# Test_Pour_Over_1.net
KiCad netlist of a schematic drawn in Altium Designer
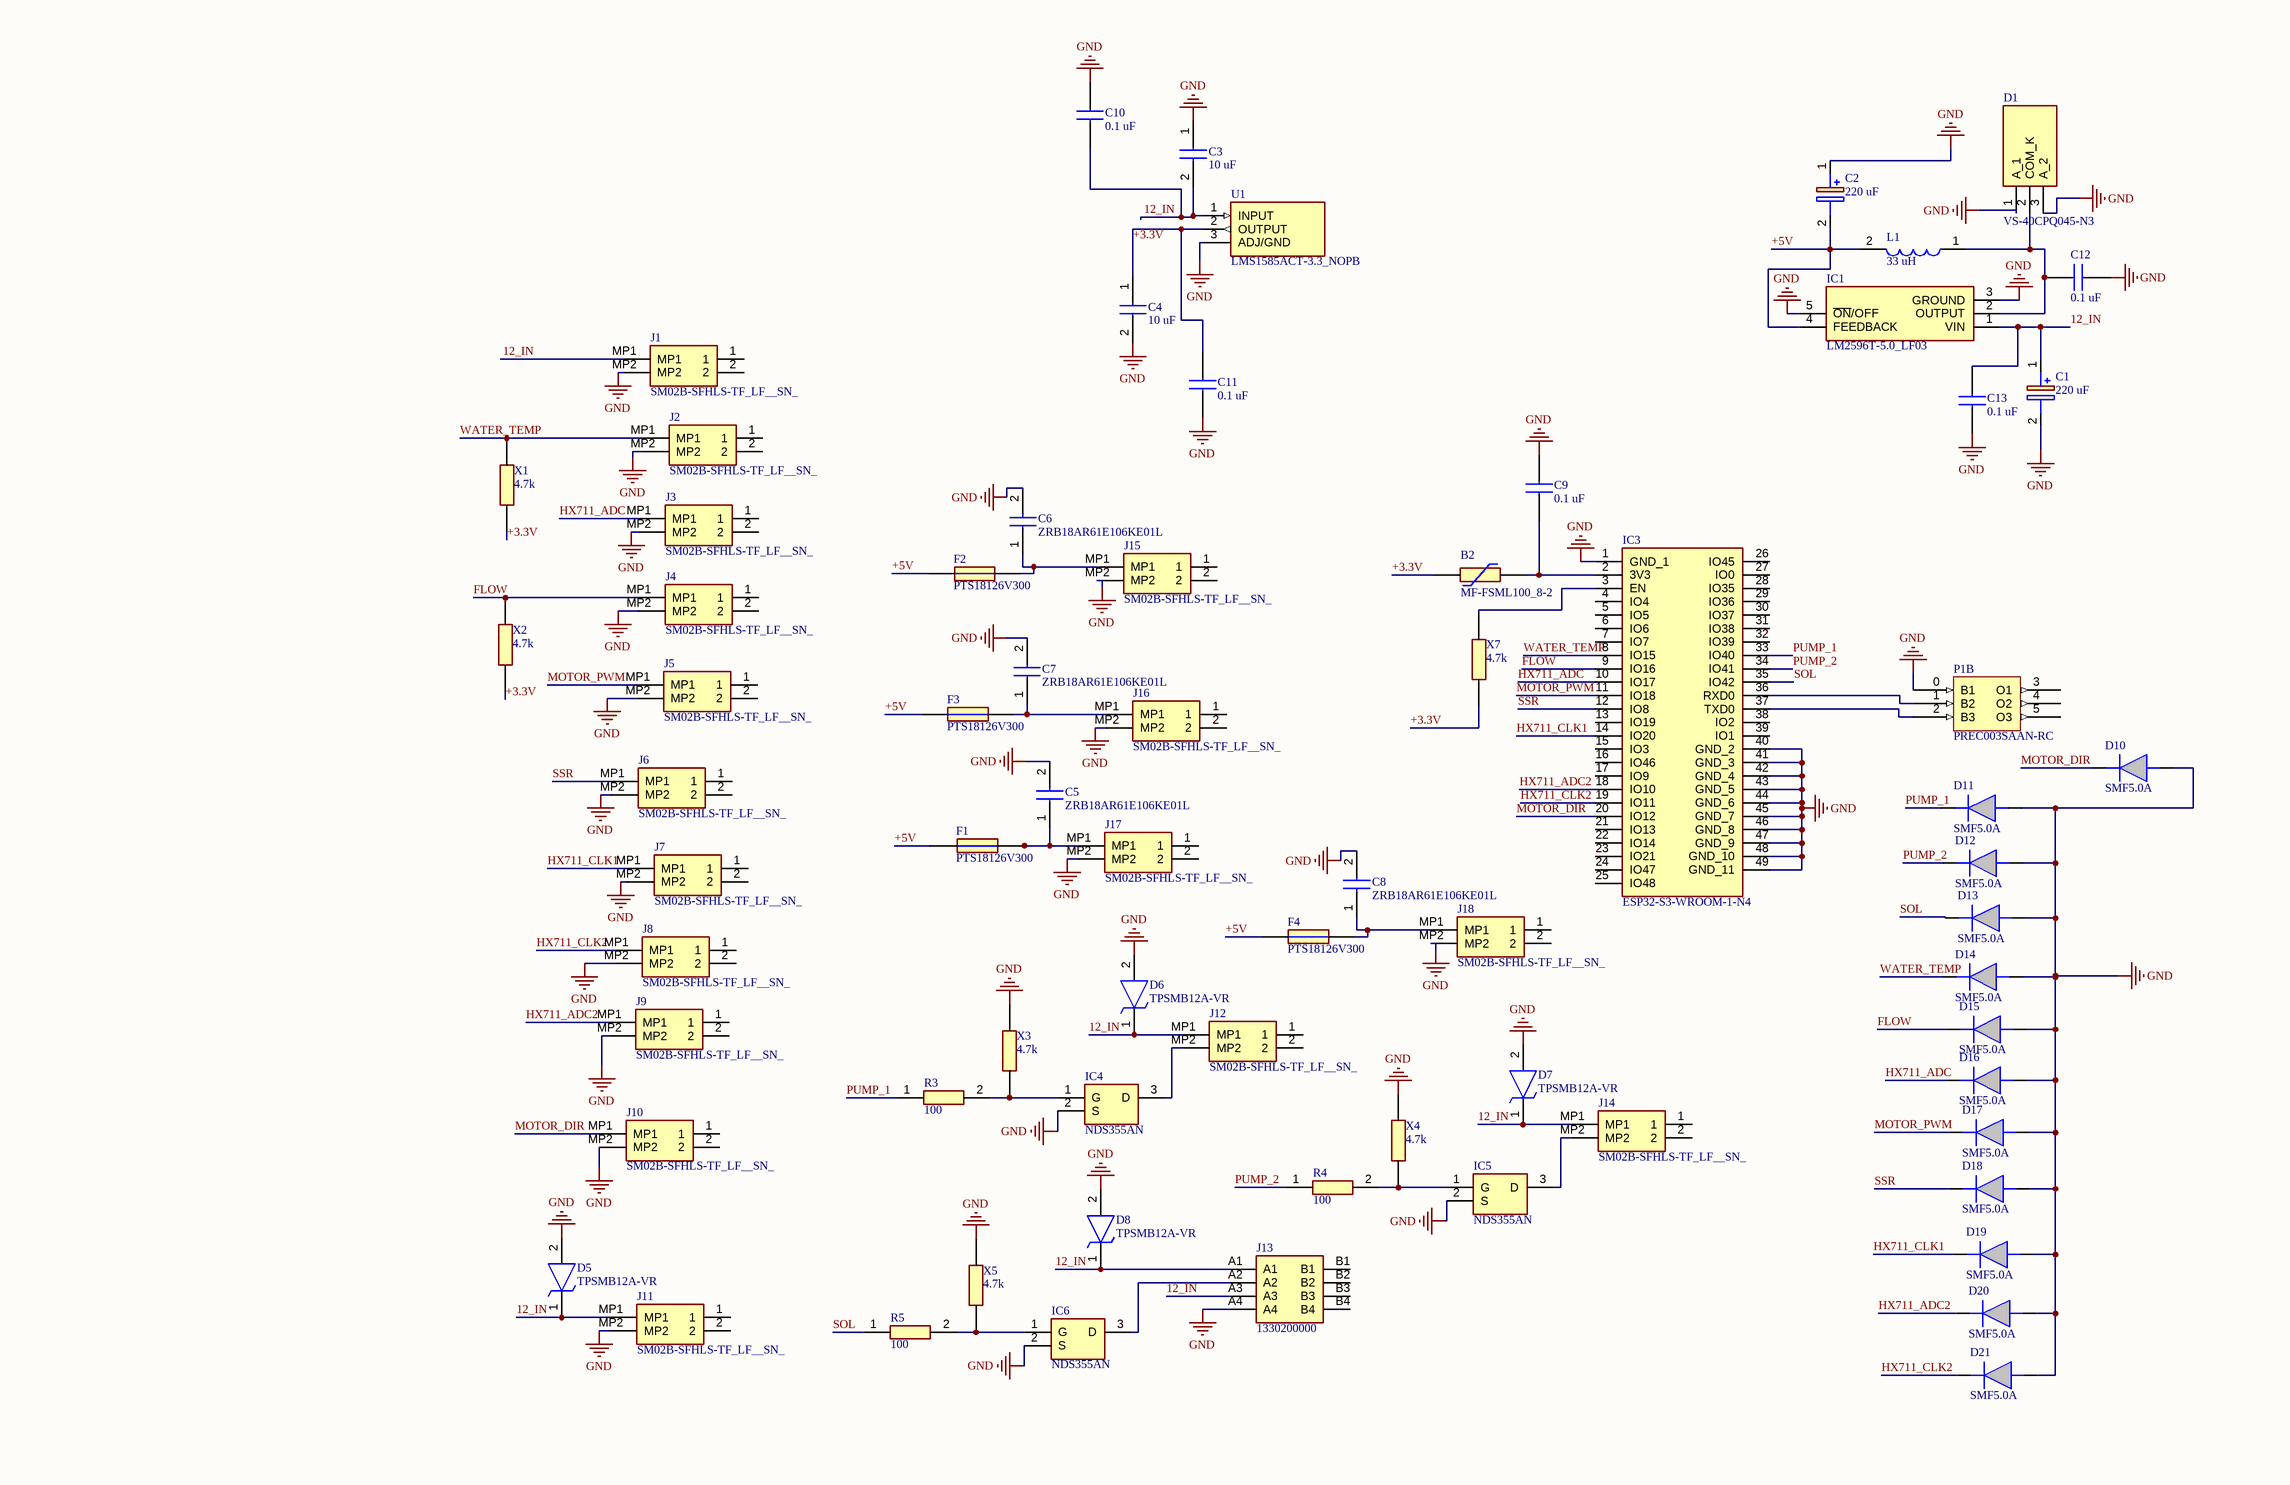
[diagram p0: Test Pour Over 1.SchDoc]

(export (version "E")
  (design (tool "Eeschema 10.0.6"))
  (components
    (comp (ref "B2")
      (value "MF-FSML100_8-2")
      (footprint "Footprints:FUSC1608X70N")
      (description "Resettable Fuses - PPTC 8V     1A")
      (fields
        (field (name "MOUSER PART NUMBER") "652-MF-FSML100/8-2")
        (field (name "MANUFACTURER_PART_NUMBER") "MF-FSML100/8-2")
      )
      (libsource (lib "Pour Over 1") (part "MF-FSML100_8-2"))
    )
    (comp (ref "C1")
      (value "220 uF")
      (footprint "Footprints:EEHZT1E331UP")
      (description "Capacitor Polarised")
      (fields
        (field (name "MANUFACTURER_PART_NUMBER") "EEE-TP1C221AP")
        (field (name "MOUSER PART NUMBER") "667-EEE-TP1C221AP")
      )
      (libsource (lib "*") (part "EEE-TP1C221AP"))
    )
    (comp (ref "C2")
      (value "220 uF")
      (footprint "Footprints:EEHZT1E331UP")
      (description "Capacitor Polarised")
      (fields
        (field (name "MANUFACTURER_PART_NUMBER") "EEE-TP1C221AP")
        (field (name "MOUSER PART NUMBER") "667-EEE-TP1C221AP")
      )
      (libsource (lib "*") (part "EEE-TP1C221AP"))
    )
    (comp (ref "C3")
      (value "10 uF")
      (footprint "Footprints:ZRB18x")
      (fields (field (name "MANUFACTURER_PART_NUMBER") "ZRB18AR61E106KE01L"))
      (libsource (lib "Pour Over 1") (part "ZRB18AR61E106KE01L"))
    )
    (comp (ref "C4")
      (value "10 uF")
      (footprint "Footprints:ZRB18x")
      (fields (field (name "MANUFACTURER_PART_NUMBER") "ZRB18AR61E106KE01L"))
      (libsource (lib "Pour Over 1") (part "ZRB18AR61E106KE01L"))
    )
    (comp (ref "C5")
      (value "ZRB18AR61E106KE01L")
      (footprint "Footprints:ZRB18x")
      (description "Capacitor")
      (libsource (lib "Pour Over 1") (part "ZRB18AR61E106KE01L"))
    )
    (comp (ref "C6")
      (value "ZRB18AR61E106KE01L")
      (footprint "Footprints:ZRB18x")
      (description "Capacitor")
      (libsource (lib "Pour Over 1") (part "ZRB18AR61E106KE01L"))
    )
    (comp (ref "C7")
      (value "ZRB18AR61E106KE01L")
      (footprint "Footprints:ZRB18x")
      (description "Capacitor")
      (libsource (lib "Pour Over 1") (part "ZRB18AR61E106KE01L"))
    )
    (comp (ref "C8")
      (value "ZRB18AR61E106KE01L")
      (footprint "Footprints:ZRB18x")
      (description "Capacitor")
      (libsource (lib "Pour Over 1") (part "ZRB18AR61E106KE01L"))
    )
    (comp (ref "C9")
      (value "0.1 uF")
      (footprint "Footprints:CAPC2012X125N")
      (fields
        (field (name "MOUSER PART NUMBER") "710-885382207007")
        (field (name "MANUFACTURER_PART_NUMBER") "885382207007")
      )
      (libsource (lib "Pour Over 1") (part "885382207007"))
    )
    (comp (ref "C10")
      (value "0.1 uF")
      (footprint "CAPC2012X125N")
      (fields
        (field (name "MOUSER PART NUMBER") "710-885382207007")
        (field (name "MANUFACTURER_PART_NUMBER") "885382207007")
      )
      (libsource (lib "Pour Over 1") (part "885382207007"))
    )
    (comp (ref "C11")
      (value "0.1 uF")
      (footprint "CAPC2012X125N")
      (fields
        (field (name "MOUSER PART NUMBER") "710-885382207007")
        (field (name "MANUFACTURER_PART_NUMBER") "885382207007")
      )
      (libsource (lib "Pour Over 1") (part "885382207007"))
    )
    (comp (ref "C12")
      (value "0.1 uF")
      (footprint "CAPC2012X125N")
      (fields
        (field (name "MOUSER PART NUMBER") "710-885382207007")
        (field (name "MANUFACTURER_PART_NUMBER") "885382207007")
      )
      (libsource (lib "Pour Over 1") (part "885382207007"))
    )
    (comp (ref "C13")
      (value "0.1 uF")
      (footprint "CAPC2012X125N")
      (fields
        (field (name "MOUSER PART NUMBER") "710-885382207007")
        (field (name "MANUFACTURER_PART_NUMBER") "885382207007")
      )
      (libsource (lib "Pour Over 1") (part "885382207007"))
    )
    (comp (ref "D1")
      (value "VS-40CPQ045-N3")
      (footprint "Footprints:TO546P531X1558X2499-3P")
      (description "Diode")
      (fields (field (name "MOUSER PART NUMBER") "78-VS-40CPQ045-N3"))
      (libsource (lib "SamacSys") (part "VS-40CPQ045-N3"))
    )
    (comp (ref "D5")
      (value "TPSMB12A-VR")
      (footprint "SamacSys:DIOM5436X244N")
      (description "TVS Diode (Uni-directional)")
      (fields (field (name "MOUSER PART NUMBER") "576-TPSMB12A-VR"))
      (libsource (lib "*") (part "TPSMB12A-VR"))
    )
    (comp (ref "D6")
      (value "TPSMB12A-VR")
      (footprint "SamacSys:DIOM5436X244N")
      (description "TVS Diode (Uni-directional)")
      (fields (field (name "MOUSER PART NUMBER") "576-TPSMB12A-VR"))
      (libsource (lib "*") (part "TPSMB12A-VR"))
    )
    (comp (ref "D7")
      (value "TPSMB12A-VR")
      (footprint "SamacSys:DIOM5436X244N")
      (description "TVS Diode (Uni-directional)")
      (fields (field (name "MOUSER PART NUMBER") "576-TPSMB12A-VR"))
      (libsource (lib "*") (part "TPSMB12A-VR"))
    )
    (comp (ref "D8")
      (value "TPSMB12A-VR")
      (footprint "SamacSys:DIOM5436X244N")
      (description "TVS Diode (Uni-directional)")
      (fields (field (name "MOUSER PART NUMBER") "576-TPSMB12A-VR"))
      (libsource (lib "*") (part "TPSMB12A-VR"))
    )
    (comp (ref "D10")
      (value "SMF5.0A")
      (footprint "Footprints:SODFL3618X110N")
      (description "LITTELFUSE - SMF5.0A - TVS DIODE, 200W, 5V, UNIDIR, SOD-123FL")
      (fields (field (name "MOUSER PART NUMBER") "576-SMF5.0A"))
      (libsource (lib "Pour Over 1") (part "SMF5.0A"))
    )
    (comp (ref "D11")
      (value "SMF5.0A")
      (footprint "Footprints:SODFL3618X110N")
      (description "LITTELFUSE - SMF5.0A - TVS DIODE, 200W, 5V, UNIDIR, SOD-123FL")
      (fields (field (name "MOUSER PART NUMBER") "576-SMF5.0A"))
      (libsource (lib "Pour Over 1") (part "SMF5.0A"))
    )
    (comp (ref "D12")
      (value "SMF5.0A")
      (footprint "Footprints:SODFL3618X110N")
      (description "LITTELFUSE - SMF5.0A - TVS DIODE, 200W, 5V, UNIDIR, SOD-123FL")
      (fields (field (name "MOUSER PART NUMBER") "576-SMF5.0A"))
      (libsource (lib "Pour Over 1") (part "SMF5.0A"))
    )
    (comp (ref "D13")
      (value "SMF5.0A")
      (footprint "Footprints:SODFL3618X110N")
      (description "LITTELFUSE - SMF5.0A - TVS DIODE, 200W, 5V, UNIDIR, SOD-123FL")
      (fields (field (name "MOUSER PART NUMBER") "576-SMF5.0A"))
      (libsource (lib "Pour Over 1") (part "SMF5.0A"))
    )
    (comp (ref "D14")
      (value "SMF5.0A")
      (footprint "Footprints:SODFL3618X110N")
      (description "LITTELFUSE - SMF5.0A - TVS DIODE, 200W, 5V, UNIDIR, SOD-123FL")
      (fields (field (name "MOUSER PART NUMBER") "576-SMF5.0A"))
      (libsource (lib "Pour Over 1") (part "SMF5.0A"))
    )
    (comp (ref "D15")
      (value "SMF5.0A")
      (footprint "Footprints:SODFL3618X110N")
      (description "LITTELFUSE - SMF5.0A - TVS DIODE, 200W, 5V, UNIDIR, SOD-123FL")
      (fields (field (name "MOUSER PART NUMBER") "576-SMF5.0A"))
      (libsource (lib "Pour Over 1") (part "SMF5.0A"))
    )
    (comp (ref "D16")
      (value "SMF5.0A")
      (footprint "Footprints:SODFL3618X110N")
      (description "LITTELFUSE - SMF5.0A - TVS DIODE, 200W, 5V, UNIDIR, SOD-123FL")
      (fields (field (name "MOUSER PART NUMBER") "576-SMF5.0A"))
      (libsource (lib "Pour Over 1") (part "SMF5.0A"))
    )
    (comp (ref "D17")
      (value "SMF5.0A")
      (footprint "Footprints:SODFL3618X110N")
      (description "LITTELFUSE - SMF5.0A - TVS DIODE, 200W, 5V, UNIDIR, SOD-123FL")
      (fields (field (name "MOUSER PART NUMBER") "576-SMF5.0A"))
      (libsource (lib "Pour Over 1") (part "SMF5.0A"))
    )
    (comp (ref "D18")
      (value "SMF5.0A")
      (footprint "Footprints:SODFL3618X110N")
      (description "LITTELFUSE - SMF5.0A - TVS DIODE, 200W, 5V, UNIDIR, SOD-123FL")
      (fields (field (name "MOUSER PART NUMBER") "576-SMF5.0A"))
      (libsource (lib "Pour Over 1") (part "SMF5.0A"))
    )
    (comp (ref "D19")
      (value "SMF5.0A")
      (footprint "Footprints:SODFL3618X110N")
      (description "LITTELFUSE - SMF5.0A - TVS DIODE, 200W, 5V, UNIDIR, SOD-123FL")
      (fields (field (name "MOUSER PART NUMBER") "576-SMF5.0A"))
      (libsource (lib "Pour Over 1") (part "SMF5.0A"))
    )
    (comp (ref "D20")
      (value "SMF5.0A")
      (footprint "Footprints:SODFL3618X110N")
      (description "LITTELFUSE - SMF5.0A - TVS DIODE, 200W, 5V, UNIDIR, SOD-123FL")
      (fields (field (name "MOUSER PART NUMBER") "576-SMF5.0A"))
      (libsource (lib "Pour Over 1") (part "SMF5.0A"))
    )
    (comp (ref "D21")
      (value "SMF5.0A")
      (footprint "Footprints:SODFL3618X110N")
      (description "LITTELFUSE - SMF5.0A - TVS DIODE, 200W, 5V, UNIDIR, SOD-123FL")
      (fields (field (name "MOUSER PART NUMBER") "576-SMF5.0A"))
      (libsource (lib "Pour Over 1") (part "SMF5.0A"))
    )
    (comp (ref "F1")
      (value "PTS18126V300")
      (footprint "Footprints:FUSC4632X120N")
      (description "PPTC SMD 1812 6V 3.0A")
      (fields (field (name "MOUSER PART NUMBER") "504-PTS18126V300"))
      (libsource (lib "Pour Over 1") (part "PTS18126V300"))
    )
    (comp (ref "F2")
      (value "PTS18126V300")
      (footprint "Footprints:FUSC4632X120N")
      (description "PPTC SMD 1812 6V 3.0A")
      (fields (field (name "MOUSER PART NUMBER") "504-PTS18126V300"))
      (libsource (lib "Pour Over 1") (part "PTS18126V300"))
    )
    (comp (ref "F3")
      (value "PTS18126V300")
      (footprint "Footprints:FUSC4632X120N")
      (description "PPTC SMD 1812 6V 3.0A")
      (fields (field (name "MOUSER PART NUMBER") "504-PTS18126V300"))
      (libsource (lib "Pour Over 1") (part "PTS18126V300"))
    )
    (comp (ref "F4")
      (value "PTS18126V300")
      (footprint "Footprints:FUSC4632X120N")
      (description "PPTC SMD 1812 6V 3.0A")
      (fields (field (name "MOUSER PART NUMBER") "504-PTS18126V300"))
      (libsource (lib "Pour Over 1") (part "PTS18126V300"))
    )
    (comp (ref "IC1")
      (value "LM2596T-5.0_LF03")
      (footprint "Footprints:TO170P470X1028X2142-5P")
      (description "Integrated Circuit")
      (fields
        (field (name "MANUFACTURER_PART_NUMBER") "LM2596T-5.0/LF03")
        (field (name "MOUSER PART NUMBER") "926-LM2596T-50/LF03")
      )
      (libsource (lib "Pour Over 1") (part "LM2596T-5.0_LF03"))
    )
    (comp (ref "IC3")
      (value "ESP32-S3-WROOM-1-N4")
      (footprint "ESP32S3WROOM1N4:ESP32S3WROOM1N4")
      (description "Integrated Circuit")
      (fields (field (name "MOUSER PART NUMBER") "356-ESP32-S3WROOM1N4"))
      (libsource (lib "SamacSys") (part "ESP32-S3-WROOM-1-N4"))
    )
    (comp (ref "IC4")
      (value "NDS355AN")
      (footprint "Footprints:SOT95P251X112-3N")
      (description "Integrated Circuit")
      (fields (field (name "MOUSER PART NUMBER") "512-NDS355AN"))
      (libsource (lib "*") (part "NDS355AN"))
    )
    (comp (ref "IC5")
      (value "NDS355AN")
      (footprint "Footprints:SOT95P251X112-3N")
      (description "Integrated Circuit")
      (fields (field (name "MOUSER PART NUMBER") "512-NDS355AN"))
      (libsource (lib "*") (part "NDS355AN"))
    )
    (comp (ref "IC6")
      (value "NDS355AN")
      (footprint "Footprints:SOT95P251X112-3N")
      (description "Integrated Circuit")
      (fields (field (name "MOUSER PART NUMBER") "512-NDS355AN"))
      (libsource (lib "*") (part "NDS355AN"))
    )
    (comp (ref "J1")
      (value "SM02B-SFHLS-TF_LF__SN_")
      (footprint "Footprints:SM02BSFHLSTFLFSN")
      (description "CONN HEADER SMD R/A 2POS 1.8MM")
      (fields
        (field (name "MANUFACTURER_PART_NUMBER") "SM02B-SFHLS-TF(LF)(SN)")
        (field (name "MOUSER PART NUMBER") "306-SM02BSFHLSTFLFSN")
      )
      (libsource (lib "Pour Over 1") (part "SM02B-SFHLS-TF_LF__SN_"))
    )
    (comp (ref "J2")
      (value "SM02B-SFHLS-TF_LF__SN_")
      (footprint "Footprints:SM02BSFHLSTFLFSN")
      (description "CONN HEADER SMD R/A 2POS 1.8MM")
      (fields
        (field (name "MANUFACTURER_PART_NUMBER") "SM02B-SFHLS-TF(LF)(SN)")
        (field (name "MOUSER PART NUMBER") "306-SM02BSFHLSTFLFSN")
      )
      (libsource (lib "Pour Over 1") (part "SM02B-SFHLS-TF_LF__SN_"))
    )
    (comp (ref "J3")
      (value "SM02B-SFHLS-TF_LF__SN_")
      (footprint "Footprints:SM02BSFHLSTFLFSN")
      (description "CONN HEADER SMD R/A 2POS 1.8MM")
      (fields
        (field (name "MANUFACTURER_PART_NUMBER") "SM02B-SFHLS-TF(LF)(SN)")
        (field (name "MOUSER PART NUMBER") "306-SM02BSFHLSTFLFSN")
      )
      (libsource (lib "Pour Over 1") (part "SM02B-SFHLS-TF_LF__SN_"))
    )
    (comp (ref "J4")
      (value "SM02B-SFHLS-TF_LF__SN_")
      (footprint "Footprints:SM02BSFHLSTFLFSN")
      (description "CONN HEADER SMD R/A 2POS 1.8MM")
      (fields
        (field (name "MANUFACTURER_PART_NUMBER") "SM02B-SFHLS-TF(LF)(SN)")
        (field (name "MOUSER PART NUMBER") "306-SM02BSFHLSTFLFSN")
      )
      (libsource (lib "Pour Over 1") (part "SM02B-SFHLS-TF_LF__SN_"))
    )
    (comp (ref "J5")
      (value "SM02B-SFHLS-TF_LF__SN_")
      (footprint "Footprints:SM02BSFHLSTFLFSN")
      (description "CONN HEADER SMD R/A 2POS 1.8MM")
      (fields
        (field (name "MANUFACTURER_PART_NUMBER") "SM02B-SFHLS-TF(LF)(SN)")
        (field (name "MOUSER PART NUMBER") "306-SM02BSFHLSTFLFSN")
      )
      (libsource (lib "Pour Over 1") (part "SM02B-SFHLS-TF_LF__SN_"))
    )
    (comp (ref "J6")
      (value "SM02B-SFHLS-TF_LF__SN_")
      (footprint "Footprints:SM02BSFHLSTFLFSN")
      (description "CONN HEADER SMD R/A 2POS 1.8MM")
      (fields
        (field (name "MOUSER PART NUMBER") "306-SM02BSFHLSTFLFSN")
        (field (name "MANUFACTURER_PART_NUMBER") "SM02B-SFHLS-TF(LF)(SN)")
      )
      (libsource (lib "Pour Over 1") (part "SM02B-SFHLS-TF_LF__SN_"))
    )
    (comp (ref "J7")
      (value "SM02B-SFHLS-TF_LF__SN_")
      (footprint "Footprints:SM02BSFHLSTFLFSN")
      (description "CONN HEADER SMD R/A 2POS 1.8MM")
      (fields
        (field (name "MANUFACTURER_PART_NUMBER") "SM02B-SFHLS-TF(LF)(SN)")
        (field (name "MOUSER PART NUMBER") "306-SM02BSFHLSTFLFSN")
      )
      (libsource (lib "Pour Over 1") (part "SM02B-SFHLS-TF_LF__SN_"))
    )
    (comp (ref "J8")
      (value "SM02B-SFHLS-TF_LF__SN_")
      (footprint "Footprints:SM02BSFHLSTFLFSN")
      (description "CONN HEADER SMD R/A 2POS 1.8MM")
      (fields
        (field (name "MANUFACTURER_PART_NUMBER") "SM02B-SFHLS-TF(LF)(SN)")
        (field (name "MOUSER PART NUMBER") "306-SM02BSFHLSTFLFSN")
      )
      (libsource (lib "Pour Over 1") (part "SM02B-SFHLS-TF_LF__SN_"))
    )
    (comp (ref "J9")
      (value "SM02B-SFHLS-TF_LF__SN_")
      (footprint "Footprints:SM02BSFHLSTFLFSN")
      (description "CONN HEADER SMD R/A 2POS 1.8MM")
      (fields
        (field (name "MANUFACTURER_PART_NUMBER") "SM02B-SFHLS-TF(LF)(SN)")
        (field (name "MOUSER PART NUMBER") "306-SM02BSFHLSTFLFSN")
      )
      (libsource (lib "Pour Over 1") (part "SM02B-SFHLS-TF_LF__SN_"))
    )
    (comp (ref "J10")
      (value "SM02B-SFHLS-TF_LF__SN_")
      (footprint "Footprints:SM02BSFHLSTFLFSN")
      (description "CONN HEADER SMD R/A 2POS 1.8MM")
      (fields
        (field (name "MANUFACTURER_PART_NUMBER") "SM02B-SFHLS-TF(LF)(SN)")
        (field (name "MOUSER PART NUMBER") "306-SM02BSFHLSTFLFSN")
      )
      (libsource (lib "Pour Over 1") (part "SM02B-SFHLS-TF_LF__SN_"))
    )
    (comp (ref "J11")
      (value "SM02B-SFHLS-TF_LF__SN_")
      (footprint "Footprints:SM02BSFHLSTFLFSN")
      (description "CONN HEADER SMD R/A 2POS 1.8MM")
      (fields
        (field (name "MOUSER PART NUMBER") "306-SM02BSFHLSTFLFSN")
        (field (name "MANUFACTURER_PART_NUMBER") "SM02B-SFHLS-TF(LF)(SN)")
      )
      (libsource (lib "Pour Over 1") (part "SM02B-SFHLS-TF_LF__SN_"))
    )
    (comp (ref "J12")
      (value "SM02B-SFHLS-TF_LF__SN_")
      (footprint "Footprints:SM02BSFHLSTFLFSN")
      (description "CONN HEADER SMD R/A 2POS 1.8MM")
      (fields
        (field (name "MOUSER PART NUMBER") "306-SM02BSFHLSTFLFSN")
        (field (name "MANUFACTURER_PART_NUMBER") "SM02B-SFHLS-TF(LF)(SN)")
      )
      (libsource (lib "Pour Over 1") (part "SM02B-SFHLS-TF_LF__SN_"))
    )
    (comp (ref "J13")
      (value "1330200000")
      (footprint "Footprints:1330200000")
      (description "Connector")
      (fields (field (name "MOUSER PART NUMBER") "470-1330200000"))
      (libsource (lib "*") (part "1330200000"))
    )
    (comp (ref "J14")
      (value "SM02B-SFHLS-TF_LF__SN_")
      (footprint "Footprints:SM02BSFHLSTFLFSN")
      (description "CONN HEADER SMD R/A 2POS 1.8MM")
      (fields
        (field (name "MOUSER PART NUMBER") "306-SM02BSFHLSTFLFSN")
        (field (name "MANUFACTURER_PART_NUMBER") "SM02B-SFHLS-TF(LF)(SN)")
      )
      (libsource (lib "Pour Over 1") (part "SM02B-SFHLS-TF_LF__SN_"))
    )
    (comp (ref "J15")
      (value "SM02B-SFHLS-TF_LF__SN_")
      (footprint "Footprints:SM02BSFHLSTFLFSN")
      (description "CONN HEADER SMD R/A 2POS 1.8MM")
      (fields
        (field (name "MOUSER PART NUMBER") "306-SM02BSFHLSTFLFSN")
        (field (name "MANUFACTURER_PART_NUMBER") "SM02B-SFHLS-TF(LF)(SN)")
      )
      (libsource (lib "Pour Over 1") (part "SM02B-SFHLS-TF_LF__SN_"))
    )
    (comp (ref "J16")
      (value "SM02B-SFHLS-TF_LF__SN_")
      (footprint "Footprints:SM02BSFHLSTFLFSN")
      (description "CONN HEADER SMD R/A 2POS 1.8MM")
      (fields
        (field (name "MOUSER PART NUMBER") "306-SM02BSFHLSTFLFSN")
        (field (name "MANUFACTURER_PART_NUMBER") "SM02B-SFHLS-TF(LF)(SN)")
      )
      (libsource (lib "Pour Over 1") (part "SM02B-SFHLS-TF_LF__SN_"))
    )
    (comp (ref "J17")
      (value "SM02B-SFHLS-TF_LF__SN_")
      (footprint "Footprints:SM02BSFHLSTFLFSN")
      (description "CONN HEADER SMD R/A 2POS 1.8MM")
      (fields
        (field (name "MOUSER PART NUMBER") "306-SM02BSFHLSTFLFSN")
        (field (name "MANUFACTURER_PART_NUMBER") "SM02B-SFHLS-TF(LF)(SN)")
      )
      (libsource (lib "Pour Over 1") (part "SM02B-SFHLS-TF_LF__SN_"))
    )
    (comp (ref "J18")
      (value "SM02B-SFHLS-TF_LF__SN_")
      (footprint "Footprints:SM02BSFHLSTFLFSN")
      (description "CONN HEADER SMD R/A 2POS 1.8MM")
      (fields
        (field (name "MOUSER PART NUMBER") "306-SM02BSFHLSTFLFSN")
        (field (name "MANUFACTURER_PART_NUMBER") "SM02B-SFHLS-TF(LF)(SN)")
      )
      (libsource (lib "Pour Over 1") (part "SM02B-SFHLS-TF_LF__SN_"))
    )
    (comp (ref "L1")
      (value "33 uH")
      (footprint "Footprints:INDPM8680X400N")
      (description "Inductor")
      (fields (field (name "MANUFACTURER_PART_NUMBER") "F1F2-0804-330M"))
      (libsource (lib "Pour Over 1") (part "F1F2-0804-330M"))
    )
    (comp (ref "P1")
      (value "PREC003SAAN-RC")
      (footprint "PCBComponent_1")
      (description "ESP32 USB Connector")
      (libsource (lib "Pour Over 1") (part "PREC003SAAN-RC"))
    )
    (comp (ref "R3")
      (value "100")
      (footprint "Footprints:RESC2012X55N")
      (description "Resistor")
      (fields
        (field (name "MANUFACTURER_PART_NUMBER") "TNPW0805100RBEEA")
        (field (name "MOUSER PART NUMBER") "71-TNPW0805100RBEEA")
      )
      (libsource (lib "*") (part "TNPW0805100RBEEA"))
    )
    (comp (ref "R4")
      (value "100")
      (footprint "Footprints:RESC2012X55N")
      (description "Resistor")
      (fields
        (field (name "MANUFACTURER_PART_NUMBER") "TNPW0805100RBEEA")
        (field (name "MOUSER PART NUMBER") "71-TNPW0805100RBEEA")
      )
      (libsource (lib "*") (part "TNPW0805100RBEEA"))
    )
    (comp (ref "R5")
      (value "100")
      (footprint "Footprints:RESC2012X55N")
      (description "Resistor")
      (fields
        (field (name "MANUFACTURER_PART_NUMBER") "TNPW0805100RBEEA")
        (field (name "MOUSER PART NUMBER") "71-TNPW0805100RBEEA")
      )
      (libsource (lib "*") (part "TNPW0805100RBEEA"))
    )
    (comp (ref "U1")
      (value "LMS1585ACT-3.3_NOPB")
      (footprint "Footprints:TO254P470X1028X1955-3P")
      (description "Undefined or Miscellaneous")
      (fields
        (field (name "MANUFACTURER_PART_NUMBER") "LMS1585ACT-3.3/NOPB")
        (field (name "MOUSER PART NUMBER") "926-LMS1585ACT33NOPB")
      )
      (libsource (lib "Pour Over 1") (part "LMS1585ACT-3.3_NOPB"))
    )
    (comp (ref "X1")
      (value "4.7k")
      (footprint "Footprints:RESC2012X65N")
      (fields
        (field (name "MOUSER PART NUMBER") "279-CPF0805B4K7E1")
        (field (name "MANUFACTURER_PART_NUMBER") "CPF0805B4K7E1")
      )
      (libsource (lib "") (part "CPF0805B4K7E1_1"))
    )
    (comp (ref "X2")
      (value "4.7k")
      (footprint "Footprints:RESC2012X65N")
      (fields
        (field (name "MOUSER PART NUMBER") "279-CPF0805B4K7E1")
        (field (name "MANUFACTURER_PART_NUMBER") "CPF0805B4K7E1")
      )
      (libsource (lib "") (part "CPF0805B4K7E1_1"))
    )
    (comp (ref "X3")
      (value "4.7k")
      (footprint "Footprints:RESC2012X65N")
      (fields
        (field (name "MOUSER PART NUMBER") "279-CPF0805B4K7E1")
        (field (name "MANUFACTURER_PART_NUMBER") "CPF0805B4K7E1")
      )
      (libsource (lib "Pour Over 1") (part "CPF0805B4K7E1"))
    )
    (comp (ref "X4")
      (value "4.7k")
      (footprint "Footprints:RESC2012X65N")
      (fields
        (field (name "MOUSER PART NUMBER") "279-CPF0805B4K7E1")
        (field (name "MANUFACTURER_PART_NUMBER") "CPF0805B4K7E1")
      )
      (libsource (lib "Pour Over 1") (part "CPF0805B4K7E1"))
    )
    (comp (ref "X5")
      (value "4.7k")
      (footprint "Footprints:RESC2012X65N")
      (fields
        (field (name "MOUSER PART NUMBER") "279-CPF0805B4K7E1")
        (field (name "MANUFACTURER_PART_NUMBER") "CPF0805B4K7E1")
      )
      (libsource (lib "Pour Over 1") (part "CPF0805B4K7E1"))
    )
    (comp (ref "X7")
      (value "4.7k")
      (footprint "Footprints:RESC2012X65N")
      (fields
        (field (name "MOUSER PART NUMBER") "279-CPF0805B4K7E1")
        (field (name "MANUFACTURER_PART_NUMBER") "CPF0805B4K7E1")
      )
      (libsource (lib "") (part "CPF0805B4K7E1_1"))
    )
  )
  (nets
    (net (code "1") (name "/+3.3V") (class "Default")
      (node (ref "B2") (pin "1") (pinfunction "1_1") (pintype "passive"))
      (node (ref "C11") (pin "2") (pinfunction "2_2") (pintype "passive"))
      (node (ref "C4") (pin "1") (pinfunction "1_1") (pintype "passive"))
      (node (ref "U1") (pin "2") (pinfunction "OUTPUT_2") (pintype "output"))
      (node (ref "X1") (pin "2") (pinfunction "2_2") (pintype "passive"))
      (node (ref "X2") (pin "2") (pinfunction "2_2") (pintype "passive"))
      (node (ref "X7") (pin "2") (pinfunction "2_2") (pintype "passive"))
    )
    (net (code "2") (name "/+5V") (class "Default")
      (node (ref "C2") (pin "2") (pinfunction "-_2") (pintype "passive"))
      (node (ref "F1") (pin "1") (pinfunction "1_1") (pintype "passive"))
      (node (ref "F2") (pin "1") (pinfunction "1_1") (pintype "passive"))
      (node (ref "F3") (pin "1") (pinfunction "1_1") (pintype "passive"))
      (node (ref "F4") (pin "1") (pinfunction "1_1") (pintype "passive"))
      (node (ref "IC1") (pin "4") (pinfunction "FEEDBACK_4") (pintype "passive"))
      (node (ref "L1") (pin "2") (pinfunction "2_2") (pintype "passive"))
    )
    (net (code "3") (name "/12_IN") (class "Default")
      (node (ref "C1") (pin "1") (pinfunction "+_1") (pintype "passive"))
      (node (ref "C10") (pin "1") (pinfunction "1_1") (pintype "passive"))
      (node (ref "C13") (pin "2") (pinfunction "2_2") (pintype "passive"))
      (node (ref "C3") (pin "2") (pinfunction "2_2") (pintype "passive"))
      (node (ref "D5") (pin "1") (pinfunction "K_1") (pintype "passive"))
      (node (ref "D6") (pin "1") (pinfunction "K_1") (pintype "passive"))
      (node (ref "D7") (pin "1") (pinfunction "K_1") (pintype "passive"))
      (node (ref "D8") (pin "1") (pinfunction "K_1") (pintype "passive"))
      (node (ref "IC1") (pin "1") (pinfunction "VIN_1") (pintype "passive"))
      (node (ref "J1") (pin "MP1") (pinfunction "MP1_MP1") (pintype "passive"))
      (node (ref "J11") (pin "MP1") (pinfunction "MP1_MP1") (pintype "passive"))
      (node (ref "J12") (pin "MP1") (pinfunction "MP1_MP1") (pintype "passive"))
      (node (ref "J13") (pin "A1") (pinfunction "A1_A1") (pintype "passive"))
      (node (ref "J13") (pin "A3") (pinfunction "A3_A3") (pintype "passive"))
      (node (ref "J14") (pin "MP1") (pinfunction "MP1_MP1") (pintype "passive"))
      (node (ref "U1") (pin "1") (pinfunction "INPUT_1") (pintype "input"))
    )
    (net (code "4") (name "/FLOW") (class "Default")
      (node (ref "D15") (pin "1") (pinfunction "K_1") (pintype "passive"))
      (node (ref "IC3") (pin "9") (pinfunction "IO16_9") (pintype "passive"))
      (node (ref "J4") (pin "MP1") (pinfunction "MP1_MP1") (pintype "passive"))
      (node (ref "X2") (pin "1") (pinfunction "1_1") (pintype "passive"))
    )
    (net (code "5") (name "/HX711_ADC") (class "Default")
      (node (ref "D16") (pin "1") (pinfunction "K_1") (pintype "passive"))
      (node (ref "IC3") (pin "10") (pinfunction "IO17_10") (pintype "passive"))
      (node (ref "J3") (pin "MP1") (pinfunction "MP1_MP1") (pintype "passive"))
    )
    (net (code "6") (name "/HX711_ADC2") (class "Default")
      (node (ref "D20") (pin "1") (pinfunction "K_1") (pintype "passive"))
      (node (ref "IC3") (pin "18") (pinfunction "IO10_18") (pintype "passive"))
      (node (ref "J9") (pin "MP1") (pinfunction "MP1_MP1") (pintype "passive"))
    )
    (net (code "7") (name "/HX711_CLK1") (class "Default")
      (node (ref "D19") (pin "1") (pinfunction "K_1") (pintype "passive"))
      (node (ref "IC3") (pin "14") (pinfunction "IO20_14") (pintype "passive"))
      (node (ref "J7") (pin "MP1") (pinfunction "MP1_MP1") (pintype "passive"))
    )
    (net (code "8") (name "/HX711_CLK2") (class "Default")
      (node (ref "D21") (pin "1") (pinfunction "K_1") (pintype "passive"))
      (node (ref "IC3") (pin "19") (pinfunction "IO11_19") (pintype "passive"))
      (node (ref "J8") (pin "MP1") (pinfunction "MP1_MP1") (pintype "passive"))
    )
    (net (code "9") (name "/MOTOR_DIR") (class "Default")
      (node (ref "D10") (pin "1") (pinfunction "K_1") (pintype "passive"))
      (node (ref "IC3") (pin "20") (pinfunction "IO12_20") (pintype "passive"))
      (node (ref "J10") (pin "MP1") (pinfunction "MP1_MP1") (pintype "passive"))
    )
    (net (code "10") (name "/MOTOR_PWM") (class "Default")
      (node (ref "D17") (pin "1") (pinfunction "K_1") (pintype "passive"))
      (node (ref "IC3") (pin "11") (pinfunction "IO18_11") (pintype "passive"))
      (node (ref "J5") (pin "MP1") (pinfunction "MP1_MP1") (pintype "passive"))
    )
    (net (code "11") (name "/PUMP_1") (class "Default")
      (node (ref "D11") (pin "1") (pinfunction "K_1") (pintype "passive"))
      (node (ref "IC3") (pin "33") (pinfunction "IO40_33") (pintype "passive"))
      (node (ref "R3") (pin "1") (pinfunction "1_1") (pintype "passive"))
    )
    (net (code "12") (name "/PUMP_2") (class "Default")
      (node (ref "D12") (pin "1") (pinfunction "K_1") (pintype "passive"))
      (node (ref "IC3") (pin "34") (pinfunction "IO41_34") (pintype "passive"))
      (node (ref "R4") (pin "1") (pinfunction "1_1") (pintype "passive"))
    )
    (net (code "13") (name "/SOL") (class "Default")
      (node (ref "D13") (pin "1") (pinfunction "K_1") (pintype "passive"))
      (node (ref "IC3") (pin "35") (pinfunction "IO42_35") (pintype "passive"))
      (node (ref "R5") (pin "1") (pinfunction "1_1") (pintype "passive"))
    )
    (net (code "14") (name "/SSR") (class "Default")
      (node (ref "D18") (pin "1") (pinfunction "K_1") (pintype "passive"))
      (node (ref "IC3") (pin "12") (pinfunction "IO8_12") (pintype "passive"))
      (node (ref "J6") (pin "MP1") (pinfunction "MP1_MP1") (pintype "passive"))
    )
    (net (code "15") (name "/WATER_TEMP") (class "Default")
      (node (ref "D14") (pin "1") (pinfunction "K_1") (pintype "passive"))
      (node (ref "IC3") (pin "8") (pinfunction "IO15_8") (pintype "passive"))
      (node (ref "J2") (pin "MP1") (pinfunction "MP1_MP1") (pintype "passive"))
      (node (ref "X1") (pin "1") (pinfunction "1_1") (pintype "passive"))
    )
    (net (code "16") (name "GND") (class "Default")
      (node (ref "C1") (pin "2") (pinfunction "-_2") (pintype "passive"))
      (node (ref "C10") (pin "2") (pinfunction "2_2") (pintype "passive"))
      (node (ref "C11") (pin "1") (pinfunction "1_1") (pintype "passive"))
      (node (ref "C12") (pin "2") (pinfunction "2_2") (pintype "passive"))
      (node (ref "C13") (pin "1") (pinfunction "1_1") (pintype "passive"))
      (node (ref "C2") (pin "1") (pinfunction "+_1") (pintype "passive"))
      (node (ref "C3") (pin "1") (pinfunction "1_1") (pintype "passive"))
      (node (ref "C4") (pin "2") (pinfunction "2_2") (pintype "passive"))
      (node (ref "C5") (pin "2") (pinfunction "2_2") (pintype "passive"))
      (node (ref "C6") (pin "2") (pinfunction "2_2") (pintype "passive"))
      (node (ref "C7") (pin "2") (pinfunction "2_2") (pintype "passive"))
      (node (ref "C8") (pin "2") (pinfunction "2_2") (pintype "passive"))
      (node (ref "C9") (pin "1") (pinfunction "1_1") (pintype "passive"))
      (node (ref "D1") (pin "1") (pinfunction "A_1_1") (pintype "passive"))
      (node (ref "D1") (pin "3") (pinfunction "A_2_3") (pintype "passive"))
      (node (ref "D10") (pin "2") (pinfunction "A_2") (pintype "passive"))
      (node (ref "D11") (pin "2") (pinfunction "A_2") (pintype "passive"))
      (node (ref "D12") (pin "2") (pinfunction "A_2") (pintype "passive"))
      (node (ref "D13") (pin "2") (pinfunction "A_2") (pintype "passive"))
      (node (ref "D14") (pin "2") (pinfunction "A_2") (pintype "passive"))
      (node (ref "D15") (pin "2") (pinfunction "A_2") (pintype "passive"))
      (node (ref "D16") (pin "2") (pinfunction "A_2") (pintype "passive"))
      (node (ref "D17") (pin "2") (pinfunction "A_2") (pintype "passive"))
      (node (ref "D18") (pin "2") (pinfunction "A_2") (pintype "passive"))
      (node (ref "D19") (pin "2") (pinfunction "A_2") (pintype "passive"))
      (node (ref "D20") (pin "2") (pinfunction "A_2") (pintype "passive"))
      (node (ref "D21") (pin "2") (pinfunction "A_2") (pintype "passive"))
      (node (ref "D5") (pin "2") (pinfunction "A_2") (pintype "passive"))
      (node (ref "D6") (pin "2") (pinfunction "A_2") (pintype "passive"))
      (node (ref "D7") (pin "2") (pinfunction "A_2") (pintype "passive"))
      (node (ref "D8") (pin "2") (pinfunction "A_2") (pintype "passive"))
      (node (ref "IC1") (pin "3") (pinfunction "GROUND_3") (pintype "passive"))
      (node (ref "IC1") (pin "5") (pinfunction "~{ON}/OFF_5") (pintype "passive"))
      (node (ref "IC3") (pin "1") (pinfunction "GND_1_1") (pintype "passive"))
      (node (ref "IC3") (pin "40") (pinfunction "GND_2_40") (pintype "passive"))
      (node (ref "IC3") (pin "41") (pinfunction "GND_3_41") (pintype "passive"))
      (node (ref "IC3") (pin "42") (pinfunction "GND_4_42") (pintype "passive"))
      (node (ref "IC3") (pin "43") (pinfunction "GND_5_43") (pintype "passive"))
      (node (ref "IC3") (pin "44") (pinfunction "GND_6_44") (pintype "passive"))
      (node (ref "IC3") (pin "45") (pinfunction "GND_7_45") (pintype "passive"))
      (node (ref "IC3") (pin "46") (pinfunction "GND_8_46") (pintype "passive"))
      (node (ref "IC3") (pin "47") (pinfunction "GND_9_47") (pintype "passive"))
      (node (ref "IC3") (pin "48") (pinfunction "GND_10_48") (pintype "passive"))
      (node (ref "IC3") (pin "49") (pinfunction "GND_11_49") (pintype "passive"))
      (node (ref "IC4") (pin "2") (pinfunction "S_2") (pintype "passive"))
      (node (ref "IC5") (pin "2") (pinfunction "S_2") (pintype "passive"))
      (node (ref "IC6") (pin "2") (pinfunction "S_2") (pintype "passive"))
      (node (ref "J1") (pin "MP2") (pinfunction "MP2_MP2") (pintype "passive"))
      (node (ref "J10") (pin "MP2") (pinfunction "MP2_MP2") (pintype "passive"))
      (node (ref "J11") (pin "MP2") (pinfunction "MP2_MP2") (pintype "passive"))
      (node (ref "J13") (pin "A4") (pinfunction "A4_A4") (pintype "passive"))
      (node (ref "J15") (pin "MP2") (pinfunction "MP2_MP2") (pintype "passive"))
      (node (ref "J16") (pin "MP2") (pinfunction "MP2_MP2") (pintype "passive"))
      (node (ref "J17") (pin "MP2") (pinfunction "MP2_MP2") (pintype "passive"))
      (node (ref "J18") (pin "MP2") (pinfunction "MP2_MP2") (pintype "passive"))
      (node (ref "J2") (pin "MP2") (pinfunction "MP2_MP2") (pintype "passive"))
      (node (ref "J3") (pin "MP2") (pinfunction "MP2_MP2") (pintype "passive"))
      (node (ref "J4") (pin "MP2") (pinfunction "MP2_MP2") (pintype "passive"))
      (node (ref "J5") (pin "MP2") (pinfunction "MP2_MP2") (pintype "passive"))
      (node (ref "J6") (pin "MP2") (pinfunction "MP2_MP2") (pintype "passive"))
      (node (ref "J7") (pin "MP2") (pinfunction "MP2_MP2") (pintype "passive"))
      (node (ref "J8") (pin "MP2") (pinfunction "MP2_MP2") (pintype "passive"))
      (node (ref "J9") (pin "MP2") (pinfunction "MP2_MP2") (pintype "passive"))
      (node (ref "P1") (pin "0") (pinfunction "B1_0") (pintype "input"))
      (node (ref "U1") (pin "3") (pinfunction "ADJ/GND_3") (pintype "power_in"))
      (node (ref "X3") (pin "2") (pinfunction "2_2") (pintype "passive"))
      (node (ref "X4") (pin "2") (pinfunction "2_2") (pintype "passive"))
      (node (ref "X5") (pin "2") (pinfunction "2_2") (pintype "passive"))
    )
    (net (code "17") (name "Net-(C5-Pad1)") (class "Default")
      (node (ref "C5") (pin "1") (pinfunction "1_1") (pintype "passive"))
      (node (ref "F1") (pin "2") (pinfunction "2_2") (pintype "passive"))
      (node (ref "J17") (pin "MP1") (pinfunction "MP1_MP1") (pintype "passive"))
    )
    (net (code "18") (name "Net-(C6-Pad1)") (class "Default")
      (node (ref "C6") (pin "1") (pinfunction "1_1") (pintype "passive"))
      (node (ref "F2") (pin "2") (pinfunction "2_2") (pintype "passive"))
      (node (ref "J15") (pin "MP1") (pinfunction "MP1_MP1") (pintype "passive"))
    )
    (net (code "19") (name "Net-(C7-Pad1)") (class "Default")
      (node (ref "C7") (pin "1") (pinfunction "1_1") (pintype "passive"))
      (node (ref "F3") (pin "2") (pinfunction "2_2") (pintype "passive"))
      (node (ref "J16") (pin "MP1") (pinfunction "MP1_MP1") (pintype "passive"))
    )
    (net (code "20") (name "Net-(C8-Pad1)") (class "Default")
      (node (ref "C8") (pin "1") (pinfunction "1_1") (pintype "passive"))
      (node (ref "F4") (pin "2") (pinfunction "2_2") (pintype "passive"))
      (node (ref "J18") (pin "MP1") (pinfunction "MP1_MP1") (pintype "passive"))
    )
    (net (code "21") (name "Net-(D1-COM_K)") (class "Default")
      (node (ref "C12") (pin "1") (pinfunction "1_1") (pintype "passive"))
      (node (ref "D1") (pin "2") (pinfunction "COM_K_2") (pintype "passive"))
      (node (ref "IC1") (pin "2") (pinfunction "OUTPUT_2") (pintype "passive"))
      (node (ref "L1") (pin "1") (pinfunction "1_1") (pintype "passive"))
    )
    (net (code "22") (name "Net-(IC3-3V3)") (class "Default")
      (node (ref "B2") (pin "2") (pinfunction "2_2") (pintype "passive"))
      (node (ref "C9") (pin "2") (pinfunction "2_2") (pintype "passive"))
      (node (ref "IC3") (pin "2") (pinfunction "3V3_2") (pintype "passive"))
    )
    (net (code "23") (name "Net-(IC3-EN)") (class "Default")
      (node (ref "IC3") (pin "3") (pinfunction "EN_3") (pintype "passive"))
      (node (ref "X7") (pin "1") (pinfunction "1_1") (pintype "passive"))
    )
    (net (code "24") (name "Net-(IC3-RXD0)") (class "Default")
      (node (ref "IC3") (pin "36") (pinfunction "RXD0_36") (pintype "passive"))
      (node (ref "P1") (pin "1") (pinfunction "B2_1") (pintype "input"))
    )
    (net (code "25") (name "Net-(IC3-TXD0)") (class "Default")
      (node (ref "IC3") (pin "37") (pinfunction "TXD0_37") (pintype "passive"))
      (node (ref "P1") (pin "2") (pinfunction "B3_2") (pintype "input"))
    )
    (net (code "26") (name "Net-(IC4-D)") (class "Default")
      (node (ref "IC4") (pin "3") (pinfunction "D_3") (pintype "passive"))
      (node (ref "J12") (pin "MP2") (pinfunction "MP2_MP2") (pintype "passive"))
    )
    (net (code "27") (name "Net-(IC4-G)") (class "Default")
      (node (ref "IC4") (pin "1") (pinfunction "G_1") (pintype "passive"))
      (node (ref "R3") (pin "2") (pinfunction "2_2") (pintype "passive"))
      (node (ref "X3") (pin "1") (pinfunction "1_1") (pintype "passive"))
    )
    (net (code "28") (name "Net-(IC5-D)") (class "Default")
      (node (ref "IC5") (pin "3") (pinfunction "D_3") (pintype "passive"))
      (node (ref "J14") (pin "MP2") (pinfunction "MP2_MP2") (pintype "passive"))
    )
    (net (code "29") (name "Net-(IC5-G)") (class "Default")
      (node (ref "IC5") (pin "1") (pinfunction "G_1") (pintype "passive"))
      (node (ref "R4") (pin "2") (pinfunction "2_2") (pintype "passive"))
      (node (ref "X4") (pin "1") (pinfunction "1_1") (pintype "passive"))
    )
    (net (code "30") (name "Net-(IC6-D)") (class "Default")
      (node (ref "IC6") (pin "3") (pinfunction "D_3") (pintype "passive"))
      (node (ref "J13") (pin "A2") (pinfunction "A2_A2") (pintype "passive"))
    )
    (net (code "31") (name "Net-(IC6-G)") (class "Default")
      (node (ref "IC6") (pin "1") (pinfunction "G_1") (pintype "passive"))
      (node (ref "R5") (pin "2") (pinfunction "2_2") (pintype "passive"))
      (node (ref "X5") (pin "1") (pinfunction "1_1") (pintype "passive"))
    )
    (net (code "32") (name "unconnected-(IC3-IO0-Pad27)") (class "Default")
      (node (ref "IC3") (pin "27") (pinfunction "IO0_27") (pintype "passive"))
    )
    (net (code "33") (name "unconnected-(IC3-IO1-Pad39)") (class "Default")
      (node (ref "IC3") (pin "39") (pinfunction "IO1_39") (pintype "passive"))
    )
    (net (code "34") (name "unconnected-(IC3-IO2-Pad38)") (class "Default")
      (node (ref "IC3") (pin "38") (pinfunction "IO2_38") (pintype "passive"))
    )
    (net (code "35") (name "unconnected-(IC3-IO3-Pad15)") (class "Default")
      (node (ref "IC3") (pin "15") (pinfunction "IO3_15") (pintype "passive"))
    )
    (net (code "36") (name "unconnected-(IC3-IO4-Pad4)") (class "Default")
      (node (ref "IC3") (pin "4") (pinfunction "IO4_4") (pintype "passive"))
    )
    (net (code "37") (name "unconnected-(IC3-IO5-Pad5)") (class "Default")
      (node (ref "IC3") (pin "5") (pinfunction "IO5_5") (pintype "passive"))
    )
    (net (code "38") (name "unconnected-(IC3-IO6-Pad6)") (class "Default")
      (node (ref "IC3") (pin "6") (pinfunction "IO6_6") (pintype "passive"))
    )
    (net (code "39") (name "unconnected-(IC3-IO7-Pad7)") (class "Default")
      (node (ref "IC3") (pin "7") (pinfunction "IO7_7") (pintype "passive"))
    )
    (net (code "40") (name "unconnected-(IC3-IO9-Pad17)") (class "Default")
      (node (ref "IC3") (pin "17") (pinfunction "IO9_17") (pintype "passive"))
    )
    (net (code "41") (name "unconnected-(IC3-IO13-Pad21)") (class "Default")
      (node (ref "IC3") (pin "21") (pinfunction "IO13_21") (pintype "passive"))
    )
    (net (code "42") (name "unconnected-(IC3-IO14-Pad22)") (class "Default")
      (node (ref "IC3") (pin "22") (pinfunction "IO14_22") (pintype "passive"))
    )
    (net (code "43") (name "unconnected-(IC3-IO19-Pad13)") (class "Default")
      (node (ref "IC3") (pin "13") (pinfunction "IO19_13") (pintype "passive"))
    )
    (net (code "44") (name "unconnected-(IC3-IO21-Pad23)") (class "Default")
      (node (ref "IC3") (pin "23") (pinfunction "IO21_23") (pintype "passive"))
    )
    (net (code "45") (name "unconnected-(IC3-IO35-Pad28)") (class "Default")
      (node (ref "IC3") (pin "28") (pinfunction "IO35_28") (pintype "passive"))
    )
    (net (code "46") (name "unconnected-(IC3-IO36-Pad29)") (class "Default")
      (node (ref "IC3") (pin "29") (pinfunction "IO36_29") (pintype "passive"))
    )
    (net (code "47") (name "unconnected-(IC3-IO37-Pad30)") (class "Default")
      (node (ref "IC3") (pin "30") (pinfunction "IO37_30") (pintype "passive"))
    )
    (net (code "48") (name "unconnected-(IC3-IO38-Pad31)") (class "Default")
      (node (ref "IC3") (pin "31") (pinfunction "IO38_31") (pintype "passive"))
    )
    (net (code "49") (name "unconnected-(IC3-IO39-Pad32)") (class "Default")
      (node (ref "IC3") (pin "32") (pinfunction "IO39_32") (pintype "passive"))
    )
    (net (code "50") (name "unconnected-(IC3-IO45-Pad26)") (class "Default")
      (node (ref "IC3") (pin "26") (pinfunction "IO45_26") (pintype "passive"))
    )
    (net (code "51") (name "unconnected-(IC3-IO46-Pad16)") (class "Default")
      (node (ref "IC3") (pin "16") (pinfunction "IO46_16") (pintype "passive"))
    )
    (net (code "52") (name "unconnected-(IC3-IO47-Pad24)") (class "Default")
      (node (ref "IC3") (pin "24") (pinfunction "IO47_24") (pintype "passive"))
    )
    (net (code "53") (name "unconnected-(IC3-IO48-Pad25)") (class "Default")
      (node (ref "IC3") (pin "25") (pinfunction "IO48_25") (pintype "passive"))
    )
    (net (code "54") (name "unconnected-(J1-Pad1)") (class "Default")
      (node (ref "J1") (pin "1") (pinfunction "1_1") (pintype "passive"))
    )
    (net (code "55") (name "unconnected-(J1-Pad2)") (class "Default")
      (node (ref "J1") (pin "2") (pinfunction "2_2") (pintype "passive"))
    )
    (net (code "56") (name "unconnected-(J2-Pad1)") (class "Default")
      (node (ref "J2") (pin "1") (pinfunction "1_1") (pintype "passive"))
    )
    (net (code "57") (name "unconnected-(J2-Pad2)") (class "Default")
      (node (ref "J2") (pin "2") (pinfunction "2_2") (pintype "passive"))
    )
    (net (code "58") (name "unconnected-(J3-Pad1)") (class "Default")
      (node (ref "J3") (pin "1") (pinfunction "1_1") (pintype "passive"))
    )
    (net (code "59") (name "unconnected-(J3-Pad2)") (class "Default")
      (node (ref "J3") (pin "2") (pinfunction "2_2") (pintype "passive"))
    )
    (net (code "60") (name "unconnected-(J4-Pad1)") (class "Default")
      (node (ref "J4") (pin "1") (pinfunction "1_1") (pintype "passive"))
    )
    (net (code "61") (name "unconnected-(J4-Pad2)") (class "Default")
      (node (ref "J4") (pin "2") (pinfunction "2_2") (pintype "passive"))
    )
    (net (code "62") (name "unconnected-(J5-Pad1)") (class "Default")
      (node (ref "J5") (pin "1") (pinfunction "1_1") (pintype "passive"))
    )
    (net (code "63") (name "unconnected-(J5-Pad2)") (class "Default")
      (node (ref "J5") (pin "2") (pinfunction "2_2") (pintype "passive"))
    )
    (net (code "64") (name "unconnected-(J6-Pad1)") (class "Default")
      (node (ref "J6") (pin "1") (pinfunction "1_1") (pintype "passive"))
    )
    (net (code "65") (name "unconnected-(J6-Pad2)") (class "Default")
      (node (ref "J6") (pin "2") (pinfunction "2_2") (pintype "passive"))
    )
    (net (code "66") (name "unconnected-(J7-Pad1)") (class "Default")
      (node (ref "J7") (pin "1") (pinfunction "1_1") (pintype "passive"))
    )
    (net (code "67") (name "unconnected-(J7-Pad2)") (class "Default")
      (node (ref "J7") (pin "2") (pinfunction "2_2") (pintype "passive"))
    )
    (net (code "68") (name "unconnected-(J8-Pad1)") (class "Default")
      (node (ref "J8") (pin "1") (pinfunction "1_1") (pintype "passive"))
    )
    (net (code "69") (name "unconnected-(J8-Pad2)") (class "Default")
      (node (ref "J8") (pin "2") (pinfunction "2_2") (pintype "passive"))
    )
    (net (code "70") (name "unconnected-(J9-Pad1)") (class "Default")
      (node (ref "J9") (pin "1") (pinfunction "1_1") (pintype "passive"))
    )
    (net (code "71") (name "unconnected-(J9-Pad2)") (class "Default")
      (node (ref "J9") (pin "2") (pinfunction "2_2") (pintype "passive"))
    )
    (net (code "72") (name "unconnected-(J10-Pad1)") (class "Default")
      (node (ref "J10") (pin "1") (pinfunction "1_1") (pintype "passive"))
    )
    (net (code "73") (name "unconnected-(J10-Pad2)") (class "Default")
      (node (ref "J10") (pin "2") (pinfunction "2_2") (pintype "passive"))
    )
    (net (code "74") (name "unconnected-(J11-Pad1)") (class "Default")
      (node (ref "J11") (pin "1") (pinfunction "1_1") (pintype "passive"))
    )
    (net (code "75") (name "unconnected-(J11-Pad2)") (class "Default")
      (node (ref "J11") (pin "2") (pinfunction "2_2") (pintype "passive"))
    )
    (net (code "76") (name "unconnected-(J12-Pad1)") (class "Default")
      (node (ref "J12") (pin "1") (pinfunction "1_1") (pintype "passive"))
    )
    (net (code "77") (name "unconnected-(J12-Pad2)") (class "Default")
      (node (ref "J12") (pin "2") (pinfunction "2_2") (pintype "passive"))
    )
    (net (code "78") (name "unconnected-(J13-PadB1)") (class "Default")
      (node (ref "J13") (pin "B1") (pinfunction "B1_B1") (pintype "passive"))
    )
    (net (code "79") (name "unconnected-(J13-PadB2)") (class "Default")
      (node (ref "J13") (pin "B2") (pinfunction "B2_B2") (pintype "passive"))
    )
    (net (code "80") (name "unconnected-(J13-PadB3)") (class "Default")
      (node (ref "J13") (pin "B3") (pinfunction "B3_B3") (pintype "passive"))
    )
    (net (code "81") (name "unconnected-(J13-PadB4)") (class "Default")
      (node (ref "J13") (pin "B4") (pinfunction "B4_B4") (pintype "passive"))
    )
    (net (code "82") (name "unconnected-(J14-Pad1)") (class "Default")
      (node (ref "J14") (pin "1") (pinfunction "1_1") (pintype "passive"))
    )
    (net (code "83") (name "unconnected-(J14-Pad2)") (class "Default")
      (node (ref "J14") (pin "2") (pinfunction "2_2") (pintype "passive"))
    )
    (net (code "84") (name "unconnected-(J15-Pad1)") (class "Default")
      (node (ref "J15") (pin "1") (pinfunction "1_1") (pintype "passive"))
    )
    (net (code "85") (name "unconnected-(J15-Pad2)") (class "Default")
      (node (ref "J15") (pin "2") (pinfunction "2_2") (pintype "passive"))
    )
    (net (code "86") (name "unconnected-(J16-Pad1)") (class "Default")
      (node (ref "J16") (pin "1") (pinfunction "1_1") (pintype "passive"))
    )
    (net (code "87") (name "unconnected-(J16-Pad2)") (class "Default")
      (node (ref "J16") (pin "2") (pinfunction "2_2") (pintype "passive"))
    )
    (net (code "88") (name "unconnected-(J17-Pad1)") (class "Default")
      (node (ref "J17") (pin "1") (pinfunction "1_1") (pintype "passive"))
    )
    (net (code "89") (name "unconnected-(J17-Pad2)") (class "Default")
      (node (ref "J17") (pin "2") (pinfunction "2_2") (pintype "passive"))
    )
    (net (code "90") (name "unconnected-(J18-Pad1)") (class "Default")
      (node (ref "J18") (pin "1") (pinfunction "1_1") (pintype "passive"))
    )
    (net (code "91") (name "unconnected-(J18-Pad2)") (class "Default")
      (node (ref "J18") (pin "2") (pinfunction "2_2") (pintype "passive"))
    )
    (net (code "92") (name "unconnected-(P1B-O1-Pad3)") (class "Default")
      (node (ref "P1") (pin "3") (pinfunction "O1_3") (pintype "output"))
    )
    (net (code "93") (name "unconnected-(P1B-O2-Pad4)") (class "Default")
      (node (ref "P1") (pin "4") (pinfunction "O2_4") (pintype "output"))
    )
    (net (code "94") (name "unconnected-(P1B-O3-Pad5)") (class "Default")
      (node (ref "P1") (pin "5") (pinfunction "O3_5") (pintype "output"))
    )
  )
)
